# EasyEDA.net
KiCad netlist of a schematic drawn in EasyEDA
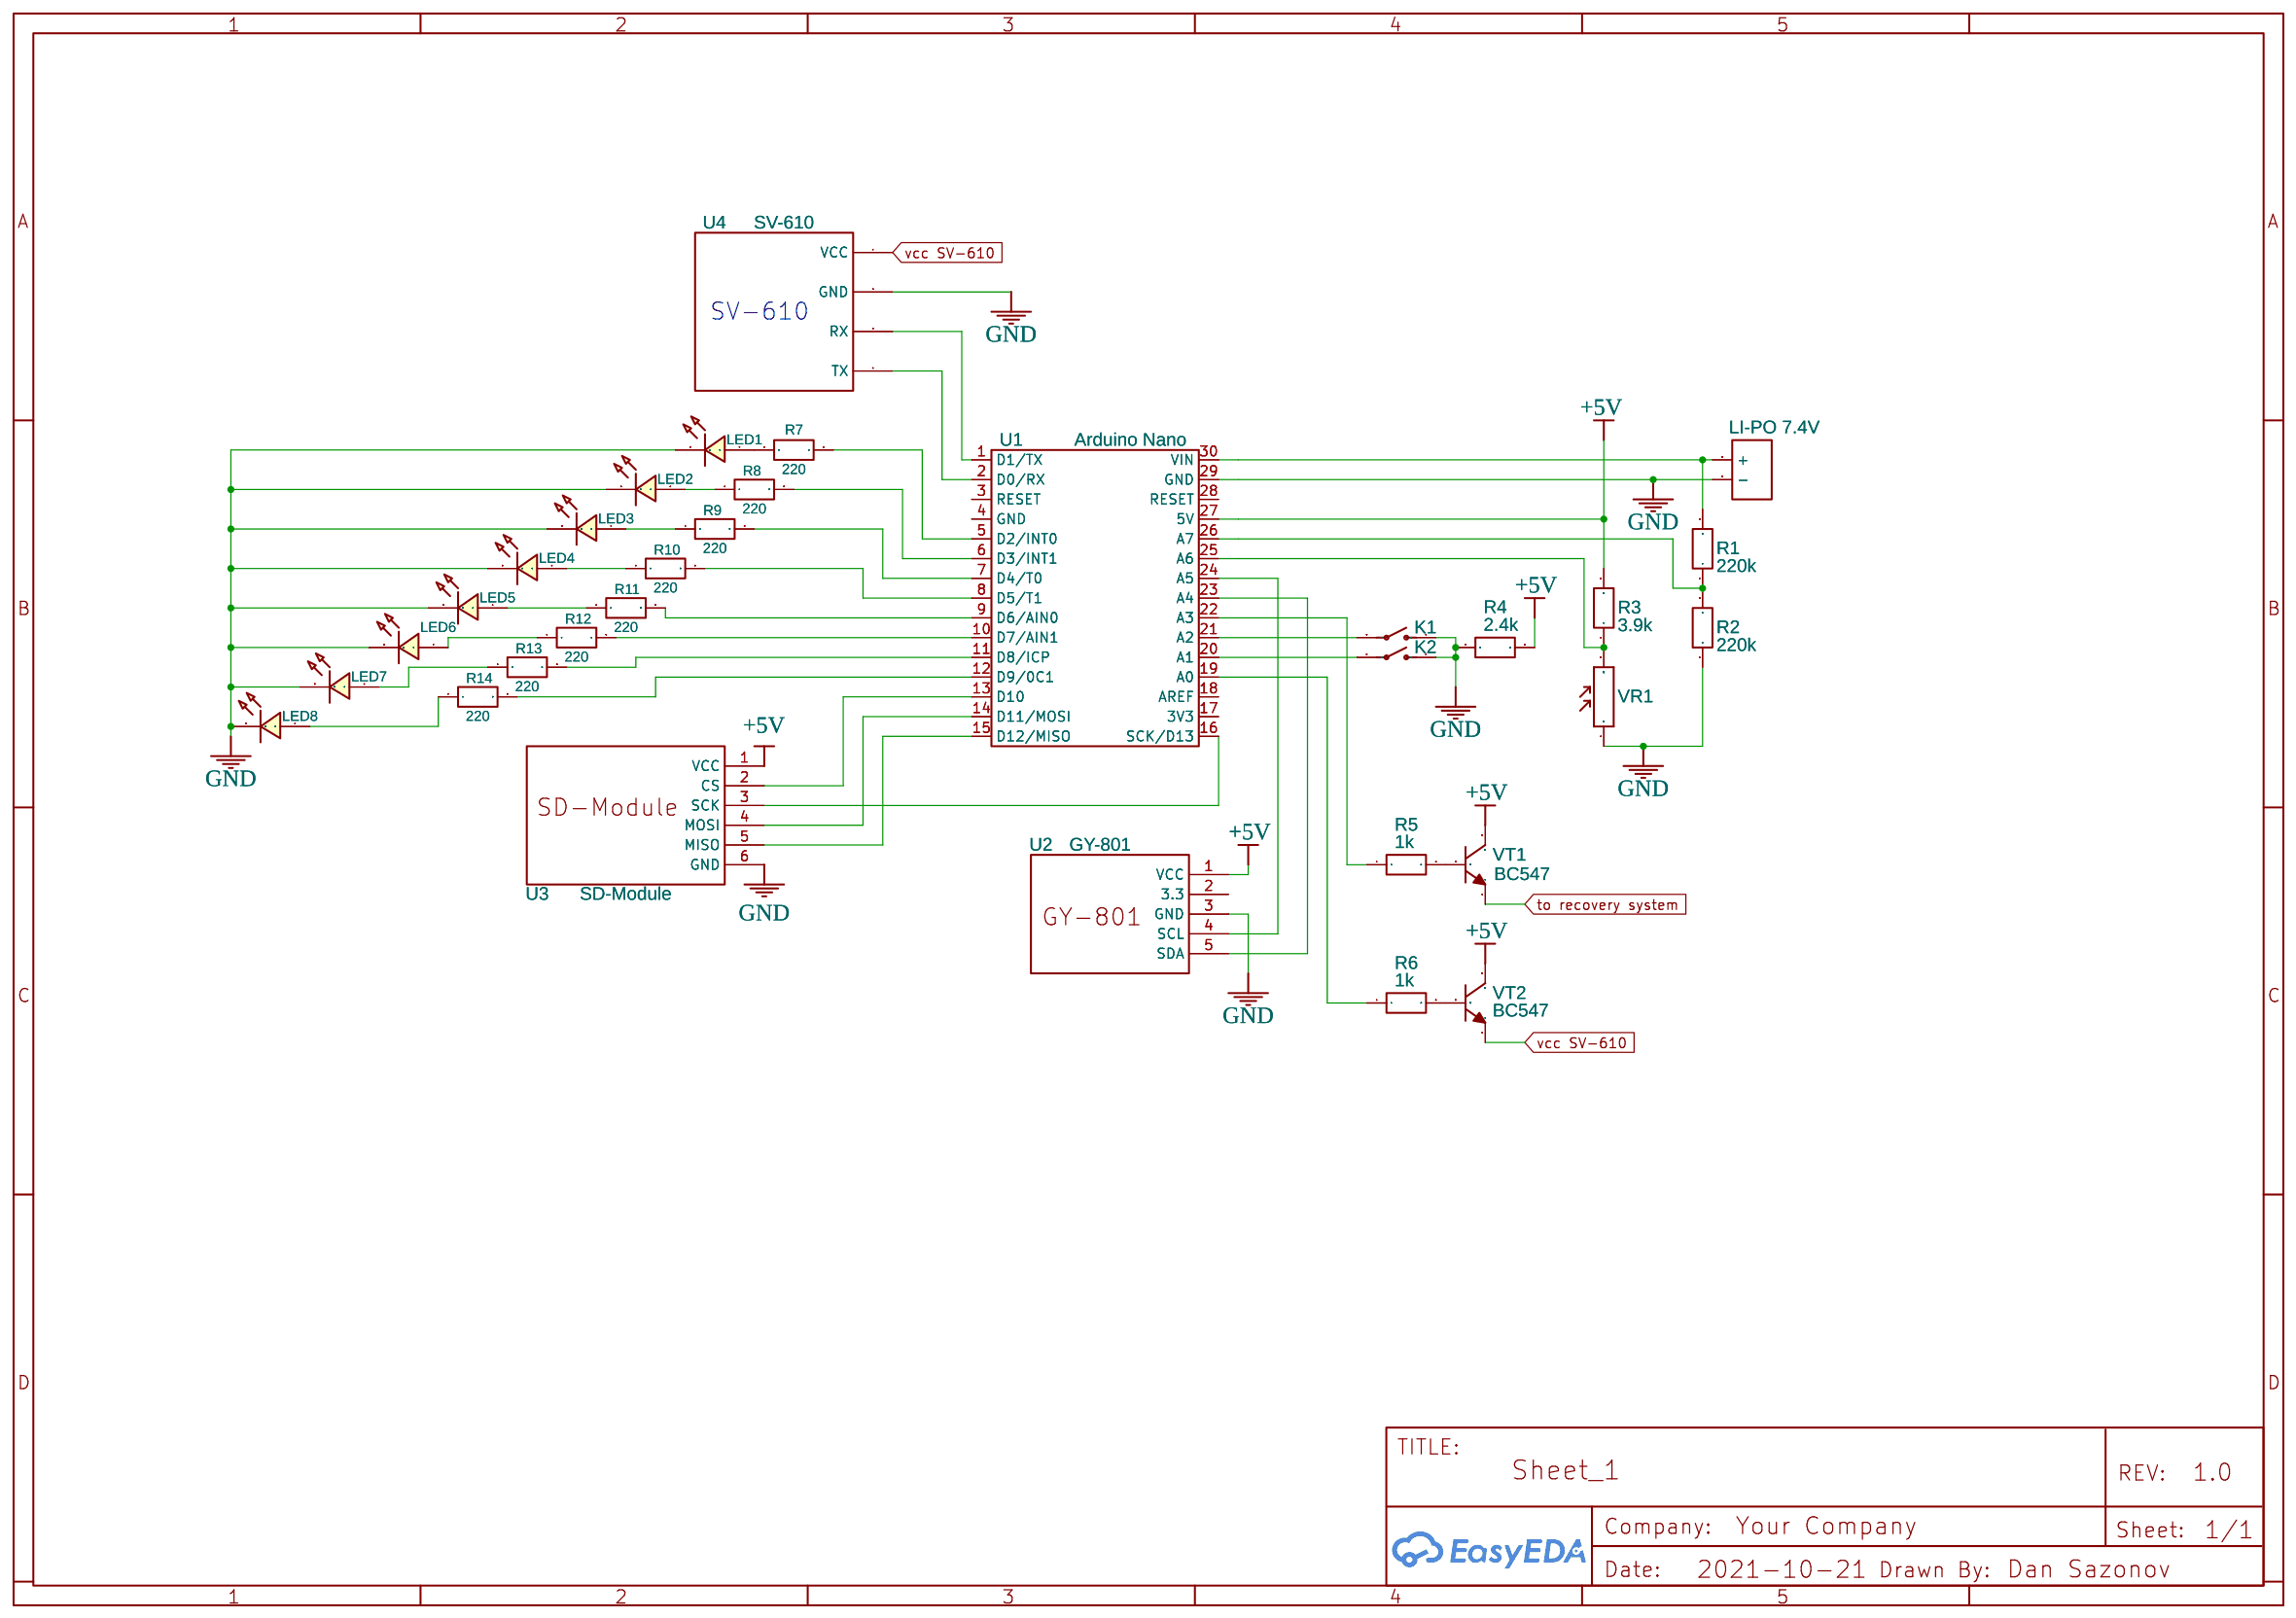
[diagram p0: schematic sheet]

(export (version "E")
  (design (tool "Eeschema 10.0.6"))
  (components
    (comp (ref "K1") (value "SWITCH-SPST-2TV") (libsource (lib "") (part "SWITCH-SPST-2TV")))
    (comp (ref "K2") (value "SWITCH-SPST-2TV") (libsource (lib "") (part "SWITCH-SPST-2TV")))
    (comp (ref "LED1")
      (value "LED-0603_R")
      (fields
        (field (name "BOM_Manufacturer Part") "19-217/R6C-AL1M2VY/3T")
        (field (name "BOM_Supplier Part") "C72044")
      )
      (libsource (lib "") (part "LED-0603_R"))
    )
    (comp (ref "LED2")
      (value "LED-0603_R")
      (fields
        (field (name "BOM_Manufacturer Part") "19-217/R6C-AL1M2VY/3T")
        (field (name "BOM_Supplier Part") "C72044")
      )
      (libsource (lib "") (part "LED-0603_R"))
    )
    (comp (ref "LED3")
      (value "LED-0603_R")
      (fields
        (field (name "BOM_Manufacturer Part") "19-217/R6C-AL1M2VY/3T")
        (field (name "BOM_Supplier Part") "C72044")
      )
      (libsource (lib "") (part "LED-0603_R"))
    )
    (comp (ref "LED4")
      (value "LED-0603_R")
      (fields
        (field (name "BOM_Manufacturer Part") "19-217/R6C-AL1M2VY/3T")
        (field (name "BOM_Supplier Part") "C72044")
      )
      (libsource (lib "") (part "LED-0603_R"))
    )
    (comp (ref "LED5")
      (value "LED-0603_R")
      (fields
        (field (name "BOM_Manufacturer Part") "19-217/R6C-AL1M2VY/3T")
        (field (name "BOM_Supplier Part") "C72044")
      )
      (libsource (lib "") (part "LED-0603_R"))
    )
    (comp (ref "LED6")
      (value "LED-0603_R")
      (fields
        (field (name "BOM_Manufacturer Part") "19-217/R6C-AL1M2VY/3T")
        (field (name "BOM_Supplier Part") "C72044")
      )
      (libsource (lib "") (part "LED-0603_R"))
    )
    (comp (ref "LED7")
      (value "LED-0603_R")
      (fields
        (field (name "BOM_Manufacturer Part") "19-217/R6C-AL1M2VY/3T")
        (field (name "BOM_Supplier Part") "C72044")
      )
      (libsource (lib "") (part "LED-0603_R"))
    )
    (comp (ref "LED8")
      (value "LED-0603_R")
      (fields
        (field (name "BOM_Manufacturer Part") "19-217/R6C-AL1M2VY/3T")
        (field (name "BOM_Supplier Part") "C72044")
      )
      (libsource (lib "") (part "LED-0603_R"))
    )
    (comp (ref "P1") (value "LI-PO 7.4V") (libsource (lib "") (part "CONN-TH_2P-P5.00")))
    (comp (ref "R1") (value "220k") (libsource (lib "") (part "R_0603_EU")))
    (comp (ref "R2") (value "220k") (libsource (lib "") (part "R_0603_EU")))
    (comp (ref "R3") (value "3.9k") (libsource (lib "") (part "R_0603_EU")))
    (comp (ref "R4") (value "2.4k") (libsource (lib "") (part "R_0603_EU_1")))
    (comp (ref "R5") (value "1k") (libsource (lib "") (part "R_0603_EU_1")))
    (comp (ref "R6") (value "1k") (libsource (lib "") (part "R_0603_EU_1")))
    (comp (ref "R7") (value "220") (libsource (lib "") (part "R_0603_EU_1")))
    (comp (ref "R8") (value "220") (libsource (lib "") (part "R_0603_EU_1")))
    (comp (ref "R9") (value "220") (libsource (lib "") (part "R_0603_EU_1")))
    (comp (ref "R10") (value "220") (libsource (lib "") (part "R_0603_EU_1")))
    (comp (ref "R11") (value "220") (libsource (lib "") (part "R_0603_EU_1")))
    (comp (ref "R12") (value "220") (libsource (lib "") (part "R_0603_EU_1")))
    (comp (ref "R13") (value "220") (libsource (lib "") (part "R_0603_EU_1")))
    (comp (ref "R14") (value "220") (libsource (lib "") (part "R_0603_EU_1")))
    (comp (ref "U1") (value "Arduino Nano") (libsource (lib "") (part "Arduino_Nano_Header")))
    (comp (ref "U2")
      (value "GY-801")
      (fields (field (name "BOM_Manufacturer Part") "GY-801 5 pin"))
      (libsource (lib "") (part "GY-801"))
    )
    (comp (ref "U3") (value "SD-Module") (libsource (lib "") (part "SD-Card-Module")))
    (comp (ref "U4") (value "SV-610") (libsource (lib "") (part "SV-610")))
    (comp (ref "VR1") (value "Photoresistor-5528") (libsource (lib "") (part "Photoresistor-5528")))
    (comp (ref "VT1")
      (value "BC547")
      (fields
        (field (name "BOM_Manufacturer Part") "2n3904S-RTK/PS")
        (field (name "BOM_Supplier Part") "C18536")
      )
      (libsource (lib "") (part "2N3904(SOT-23)"))
    )
    (comp (ref "VT2")
      (value "BC547")
      (fields
        (field (name "BOM_Manufacturer Part") "2n3904S-RTK/PS")
        (field (name "BOM_Supplier Part") "C18536")
      )
      (libsource (lib "") (part "2N3904(SOT-23)"))
    )
  )
  (nets
    (net (code "1") (name "+5V") (class "Default")
      (node (ref "R3") (pin "2") (pinfunction "2_2") (pintype "unspecified"))
      (node (ref "R4") (pin "2") (pinfunction "2_2") (pintype "unspecified"))
      (node (ref "U1") (pin "27") (pinfunction "5V_27") (pintype "unspecified"))
      (node (ref "U2") (pin "1") (pinfunction "VCC_1") (pintype "unspecified"))
      (node (ref "U3") (pin "1") (pinfunction "VCC_1") (pintype "unspecified"))
      (node (ref "VT1") (pin "3") (pinfunction "C_3") (pintype "input"))
      (node (ref "VT2") (pin "3") (pinfunction "C_3") (pintype "input"))
    )
    (net (code "2") (name "GND") (class "Default")
      (node (ref "K1") (pin "1") (pinfunction "O_1") (pintype "unspecified"))
      (node (ref "K2") (pin "1") (pinfunction "O_1") (pintype "unspecified"))
      (node (ref "LED1") (pin "2") (pinfunction "2_2") (pintype "unspecified"))
      (node (ref "LED2") (pin "2") (pinfunction "2_2") (pintype "unspecified"))
      (node (ref "LED3") (pin "2") (pinfunction "2_2") (pintype "unspecified"))
      (node (ref "LED4") (pin "2") (pinfunction "2_2") (pintype "unspecified"))
      (node (ref "LED5") (pin "2") (pinfunction "2_2") (pintype "unspecified"))
      (node (ref "LED6") (pin "2") (pinfunction "2_2") (pintype "unspecified"))
      (node (ref "LED7") (pin "2") (pinfunction "2_2") (pintype "unspecified"))
      (node (ref "LED8") (pin "2") (pinfunction "2_2") (pintype "unspecified"))
      (node (ref "P1") (pin "2") (pinfunction "-_2") (pintype "unspecified"))
      (node (ref "R2") (pin "1") (pinfunction "1_1") (pintype "unspecified"))
      (node (ref "R4") (pin "1") (pinfunction "1_1") (pintype "unspecified"))
      (node (ref "U1") (pin "29") (pinfunction "GND_29") (pintype "unspecified"))
      (node (ref "U2") (pin "3") (pinfunction "GND_3") (pintype "unspecified"))
      (node (ref "U3") (pin "6") (pinfunction "GND_6") (pintype "unspecified"))
      (node (ref "U4") (pin "3") (pinfunction "GND_3") (pintype "unspecified"))
      (node (ref "VR1") (pin "1") (pinfunction "P$1_1") (pintype "unspecified"))
    )
    (net (code "3") (name "Net-(K1-P)") (class "Default")
      (node (ref "K1") (pin "2") (pinfunction "P_2") (pintype "unspecified"))
      (node (ref "U1") (pin "21") (pinfunction "A2_21") (pintype "unspecified"))
    )
    (net (code "4") (name "Net-(K2-P)") (class "Default")
      (node (ref "K2") (pin "2") (pinfunction "P_2") (pintype "unspecified"))
      (node (ref "U1") (pin "20") (pinfunction "A1_20") (pintype "unspecified"))
    )
    (net (code "5") (name "Net-(LED1-Pad1)") (class "Default")
      (node (ref "LED1") (pin "1") (pinfunction "1_1") (pintype "unspecified"))
      (node (ref "R7") (pin "1") (pinfunction "1_1") (pintype "unspecified"))
    )
    (net (code "6") (name "Net-(LED2-Pad1)") (class "Default")
      (node (ref "LED2") (pin "1") (pinfunction "1_1") (pintype "unspecified"))
      (node (ref "R8") (pin "1") (pinfunction "1_1") (pintype "unspecified"))
    )
    (net (code "7") (name "Net-(LED3-Pad1)") (class "Default")
      (node (ref "LED3") (pin "1") (pinfunction "1_1") (pintype "unspecified"))
      (node (ref "R9") (pin "1") (pinfunction "1_1") (pintype "unspecified"))
    )
    (net (code "8") (name "Net-(LED4-Pad1)") (class "Default")
      (node (ref "LED4") (pin "1") (pinfunction "1_1") (pintype "unspecified"))
      (node (ref "R10") (pin "1") (pinfunction "1_1") (pintype "unspecified"))
    )
    (net (code "9") (name "Net-(LED5-Pad1)") (class "Default")
      (node (ref "LED5") (pin "1") (pinfunction "1_1") (pintype "unspecified"))
      (node (ref "R11") (pin "1") (pinfunction "1_1") (pintype "unspecified"))
    )
    (net (code "10") (name "Net-(LED6-Pad1)") (class "Default")
      (node (ref "LED6") (pin "1") (pinfunction "1_1") (pintype "unspecified"))
      (node (ref "R12") (pin "1") (pinfunction "1_1") (pintype "unspecified"))
    )
    (net (code "11") (name "Net-(LED7-Pad1)") (class "Default")
      (node (ref "LED7") (pin "1") (pinfunction "1_1") (pintype "unspecified"))
      (node (ref "R13") (pin "1") (pinfunction "1_1") (pintype "unspecified"))
    )
    (net (code "12") (name "Net-(LED8-Pad1)") (class "Default")
      (node (ref "LED8") (pin "1") (pinfunction "1_1") (pintype "unspecified"))
      (node (ref "R14") (pin "1") (pinfunction "1_1") (pintype "unspecified"))
    )
    (net (code "13") (name "Net-(P1-+)") (class "Default")
      (node (ref "P1") (pin "1") (pinfunction "+_1") (pintype "unspecified"))
      (node (ref "R1") (pin "2") (pinfunction "2_2") (pintype "unspecified"))
      (node (ref "U1") (pin "30") (pinfunction "VIN_30") (pintype "unspecified"))
    )
    (net (code "14") (name "Net-(U1-A0)") (class "Default")
      (node (ref "R6") (pin "1") (pinfunction "1_1") (pintype "unspecified"))
      (node (ref "U1") (pin "19") (pinfunction "A0_19") (pintype "unspecified"))
    )
    (net (code "15") (name "Net-(U1-A3)") (class "Default")
      (node (ref "R5") (pin "1") (pinfunction "1_1") (pintype "unspecified"))
      (node (ref "U1") (pin "22") (pinfunction "A3_22") (pintype "unspecified"))
    )
    (net (code "16") (name "Net-(U1-A4)") (class "Default")
      (node (ref "U1") (pin "23") (pinfunction "A4_23") (pintype "unspecified"))
      (node (ref "U2") (pin "5") (pinfunction "SDA_5") (pintype "unspecified"))
    )
    (net (code "17") (name "Net-(U1-A5)") (class "Default")
      (node (ref "U1") (pin "24") (pinfunction "A5_24") (pintype "unspecified"))
      (node (ref "U2") (pin "4") (pinfunction "SCL_4") (pintype "unspecified"))
    )
    (net (code "18") (name "Net-(U1-A6)") (class "Default")
      (node (ref "R3") (pin "1") (pinfunction "1_1") (pintype "unspecified"))
      (node (ref "U1") (pin "25") (pinfunction "A6_25") (pintype "unspecified"))
      (node (ref "VR1") (pin "2") (pinfunction "P$2_2") (pintype "unspecified"))
    )
    (net (code "19") (name "Net-(U1-A7)") (class "Default")
      (node (ref "R1") (pin "1") (pinfunction "1_1") (pintype "unspecified"))
      (node (ref "R2") (pin "2") (pinfunction "2_2") (pintype "unspecified"))
      (node (ref "U1") (pin "26") (pinfunction "A7_26") (pintype "unspecified"))
    )
    (net (code "20") (name "Net-(U1-D0{slash}RX)") (class "Default")
      (node (ref "U1") (pin "2") (pinfunction "D0/RX_2") (pintype "unspecified"))
      (node (ref "U4") (pin "1") (pinfunction "TX_1") (pintype "unspecified"))
    )
    (net (code "21") (name "Net-(U1-D1{slash}TX)") (class "Default")
      (node (ref "U1") (pin "1") (pinfunction "D1/TX_1") (pintype "unspecified"))
      (node (ref "U4") (pin "2") (pinfunction "RX_2") (pintype "unspecified"))
    )
    (net (code "22") (name "Net-(U1-D2{slash}INT0)") (class "Default")
      (node (ref "R7") (pin "2") (pinfunction "2_2") (pintype "unspecified"))
      (node (ref "U1") (pin "5") (pinfunction "D2/INT0_5") (pintype "unspecified"))
    )
    (net (code "23") (name "Net-(U1-D3{slash}INT1)") (class "Default")
      (node (ref "R8") (pin "2") (pinfunction "2_2") (pintype "unspecified"))
      (node (ref "U1") (pin "6") (pinfunction "D3/INT1_6") (pintype "unspecified"))
    )
    (net (code "24") (name "Net-(U1-D4{slash}T0)") (class "Default")
      (node (ref "R9") (pin "2") (pinfunction "2_2") (pintype "unspecified"))
      (node (ref "U1") (pin "7") (pinfunction "D4/T0_7") (pintype "unspecified"))
    )
    (net (code "25") (name "Net-(U1-D5{slash}T1)") (class "Default")
      (node (ref "R10") (pin "2") (pinfunction "2_2") (pintype "unspecified"))
      (node (ref "U1") (pin "8") (pinfunction "D5/T1_8") (pintype "unspecified"))
    )
    (net (code "26") (name "Net-(U1-D6{slash}AIN0)") (class "Default")
      (node (ref "R11") (pin "2") (pinfunction "2_2") (pintype "unspecified"))
      (node (ref "U1") (pin "9") (pinfunction "D6/AIN0_9") (pintype "unspecified"))
    )
    (net (code "27") (name "Net-(U1-D7{slash}AIN1)") (class "Default")
      (node (ref "R12") (pin "2") (pinfunction "2_2") (pintype "unspecified"))
      (node (ref "U1") (pin "10") (pinfunction "D7/AIN1_10") (pintype "unspecified"))
    )
    (net (code "28") (name "Net-(U1-D8{slash}ICP)") (class "Default")
      (node (ref "R13") (pin "2") (pinfunction "2_2") (pintype "unspecified"))
      (node (ref "U1") (pin "11") (pinfunction "D8/ICP_11") (pintype "unspecified"))
    )
    (net (code "29") (name "Net-(U1-D9{slash}0C1)") (class "Default")
      (node (ref "R14") (pin "2") (pinfunction "2_2") (pintype "unspecified"))
      (node (ref "U1") (pin "12") (pinfunction "D9/0C1_12") (pintype "unspecified"))
    )
    (net (code "30") (name "Net-(U1-D10)") (class "Default")
      (node (ref "U1") (pin "13") (pinfunction "D10_13") (pintype "unspecified"))
      (node (ref "U3") (pin "2") (pinfunction "CS_2") (pintype "unspecified"))
    )
    (net (code "31") (name "Net-(U1-D11{slash}MOSI)") (class "Default")
      (node (ref "U1") (pin "14") (pinfunction "D11/MOSI_14") (pintype "unspecified"))
      (node (ref "U3") (pin "4") (pinfunction "MOSI_4") (pintype "unspecified"))
    )
    (net (code "32") (name "Net-(U1-D12{slash}MISO)") (class "Default")
      (node (ref "U1") (pin "15") (pinfunction "D12/MISO_15") (pintype "unspecified"))
      (node (ref "U3") (pin "5") (pinfunction "MISO_5") (pintype "unspecified"))
    )
    (net (code "33") (name "Net-(U1-SCK{slash}D13)") (class "Default")
      (node (ref "U1") (pin "16") (pinfunction "SCK/D13_16") (pintype "unspecified"))
      (node (ref "U3") (pin "3") (pinfunction "SCK_3") (pintype "unspecified"))
    )
    (net (code "34") (name "Net-(VT1-B)") (class "Default")
      (node (ref "R5") (pin "2") (pinfunction "2_2") (pintype "unspecified"))
      (node (ref "VT1") (pin "2") (pinfunction "B_2") (pintype "input"))
    )
    (net (code "35") (name "Net-(VT2-B)") (class "Default")
      (node (ref "R6") (pin "2") (pinfunction "2_2") (pintype "unspecified"))
      (node (ref "VT2") (pin "2") (pinfunction "B_2") (pintype "input"))
    )
    (net (code "36") (name "to recovery system") (class "Default")
      (node (ref "VT1") (pin "1") (pinfunction "E_1") (pintype "input"))
    )
    (net (code "37") (name "unconnected-(U1-3V3-Pad17)") (class "Default")
      (node (ref "U1") (pin "17") (pinfunction "3V3_17") (pintype "unspecified"))
    )
    (net (code "38") (name "unconnected-(U1-AREF-Pad18)") (class "Default")
      (node (ref "U1") (pin "18") (pinfunction "AREF_18") (pintype "unspecified"))
    )
    (net (code "39") (name "unconnected-(U1-GND-Pad4)") (class "Default")
      (node (ref "U1") (pin "4") (pinfunction "GND_4") (pintype "unspecified"))
    )
    (net (code "40") (name "unconnected-(U1-RESET-Pad3)") (class "Default")
      (node (ref "U1") (pin "3") (pinfunction "RESET_3") (pintype "unspecified"))
    )
    (net (code "41") (name "unconnected-(U1-RESET-Pad28)") (class "Default")
      (node (ref "U1") (pin "28") (pinfunction "RESET_28") (pintype "unspecified"))
    )
    (net (code "42") (name "unconnected-(U2-3.3-Pad2)") (class "Default")
      (node (ref "U2") (pin "2") (pinfunction "3.3_2") (pintype "unspecified"))
    )
    (net (code "43") (name "vcc SV-610") (class "Default")
      (node (ref "U4") (pin "4") (pinfunction "VCC_4") (pintype "unspecified"))
      (node (ref "VT2") (pin "1") (pinfunction "E_1") (pintype "input"))
    )
  )
)
